# Uc_Ticketing_Slave.net
KiCad netlist of a schematic drawn in Altium Designer
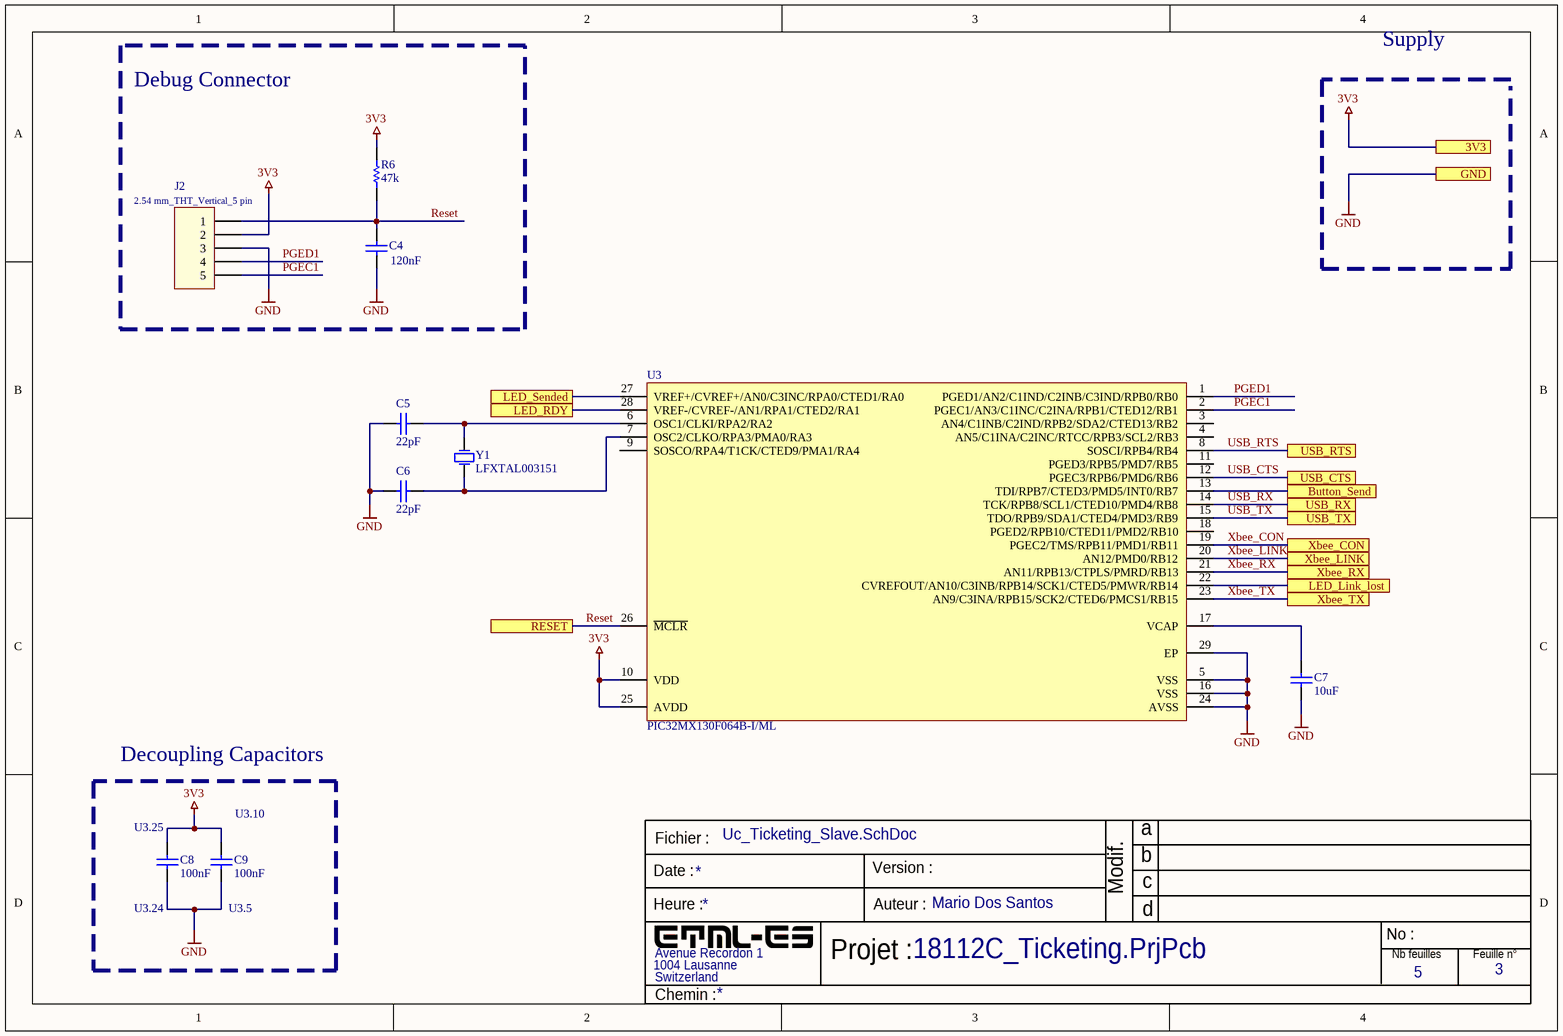
[diagram p0: Uc_Ticketing_Slave.SchDoc]

(export (version "E")
  (design (tool "Eeschema 10.0.6"))
  (components
    (comp (ref "C4")
      (value "120nF")
      (footprint "6-0805_N")
      (description "Capacitor")
      (libsource (lib "Miscellaneous Devices") (part "Cap"))
    )
    (comp (ref "C5")
      (value "22pF")
      (footprint "6-0805_N")
      (description "VJ0805Y104KNAAT")
      (libsource (lib "2126_AffichageMatriciel") (part "CMP-2007-03167-1"))
    )
    (comp (ref "C6")
      (value "22pF")
      (footprint "6-0805_N")
      (description "VJ0805Y104KNAAT")
      (libsource (lib "2126_AffichageMatriciel") (part "CMP-2007-03167-1"))
    )
    (comp (ref "C7")
      (value "10uF")
      (footprint "6-0805_N")
      (description "Capacitor")
      (libsource (lib "Miscellaneous Devices") (part "Cap"))
    )
    (comp (ref "C8")
      (value "100nF")
      (footprint "6-0805_N")
      (description "Capacitor")
      (libsource (lib "Miscellaneous Devices") (part "Cap"))
    )
    (comp (ref "C9")
      (value "100nF")
      (footprint "6-0805_N")
      (description "Capacitor")
      (libsource (lib "Miscellaneous Devices") (part "Cap"))
    )
    (comp (ref "J2")
      (value "2.54 mm_THT_Vertical_5 pin")
      (footprint "61300511121")
      (description "Pin Header WR-PHD, pitch 2.54 mm, THT, Vertical, single row, 5 pin")
      (libsource (lib "ALTIUM-PHD_2_54_THT_PIN_HEADER_6130XX11121-rev18a") (part "61300511121"))
    )
    (comp (ref "R6")
      (value "47k")
      (footprint "RESC0805(2012)_L")
      (description "100K 0.125W 5% 0805 (2012 Metric)  SMD")
      (libsource (lib "Altium Content Vault") (part "CMP-1013-00122-1"))
    )
    (comp (ref "U3")
      (value "PIC32MX130F064B-I/ML")
      (footprint "MCHP-QFN-ML28_L")
      (libsource (lib "PCB_Ticketing_Slave") (part "CMP-0048-00437-1"))
    )
    (comp (ref "Y1")
      (value "LFXTAL003151")
      (footprint "LFXTAL003151REEL")
      (description "Crystal or Oscillator")
      (libsource (lib "2126_AffichageMatriciel") (part "LFXTAL003151REEL"))
    )
  )
  (nets
    (net (code "1") (name "/Button_Send") (class "Default")
      (node (ref "U3") (pin "13") (pinfunction "TDI/RPB7/CTED3/PMD5/INT0/RB7_13") (pintype "passive"))
    )
    (net (code "2") (name "/LED_Link_lost") (class "Default")
      (node (ref "U3") (pin "22") (pinfunction "CVREFOUT/AN10/C3INB/RPB14/SCK1/CTED5/PMWR/RB14_22") (pintype "passive"))
    )
    (net (code "3") (name "/LED_RDY") (class "Default")
      (node (ref "U3") (pin "28") (pinfunction "VREF-/CVREF-/AN1/RPA1/CTED2/RA1_28") (pintype "passive"))
    )
    (net (code "4") (name "/LED_Sended") (class "Default")
      (node (ref "U3") (pin "27") (pinfunction "VREF+/CVREF+/AN0/C3INC/RPA0/CTED1/RA0_27") (pintype "passive"))
    )
    (net (code "5") (name "/PGEC1") (class "Default")
      (node (ref "J2") (pin "5") (pinfunction "5_5") (pintype "passive"))
      (node (ref "U3") (pin "2") (pinfunction "PGEC1/AN3/C1INC/C2INA/RPB1/CTED12/RB1_2") (pintype "passive"))
    )
    (net (code "6") (name "/PGED1") (class "Default")
      (node (ref "J2") (pin "4") (pinfunction "4_4") (pintype "passive"))
      (node (ref "U3") (pin "1") (pinfunction "PGED1/AN2/C1IND/C2INB/C3IND/RPB0/RB0_1") (pintype "passive"))
    )
    (net (code "7") (name "/Reset") (class "Default")
      (node (ref "C4") (pin "2") (pinfunction "2_2") (pintype "passive"))
      (node (ref "J2") (pin "1") (pinfunction "1_1") (pintype "passive"))
      (node (ref "R6") (pin "2") (pinfunction "2_2") (pintype "passive"))
      (node (ref "U3") (pin "26") (pinfunction "~{MCLR}_26") (pintype "passive"))
    )
    (net (code "8") (name "/USB_CTS") (class "Default")
      (node (ref "U3") (pin "12") (pinfunction "PGEC3/RPB6/PMD6/RB6_12") (pintype "passive"))
    )
    (net (code "9") (name "/USB_RTS") (class "Default")
      (node (ref "U3") (pin "8") (pinfunction "SOSCI/RPB4/RB4_8") (pintype "passive"))
    )
    (net (code "10") (name "/USB_RX") (class "Default")
      (node (ref "U3") (pin "14") (pinfunction "TCK/RPB8/SCL1/CTED10/PMD4/RB8_14") (pintype "passive"))
    )
    (net (code "11") (name "/USB_TX") (class "Default")
      (node (ref "U3") (pin "15") (pinfunction "TDO/RPB9/SDA1/CTED4/PMD3/RB9_15") (pintype "passive"))
    )
    (net (code "12") (name "/Xbee_CON") (class "Default")
      (node (ref "U3") (pin "19") (pinfunction "PGEC2/TMS/RPB11/PMD1/RB11_19") (pintype "passive"))
    )
    (net (code "13") (name "/Xbee_LINK") (class "Default")
      (node (ref "U3") (pin "20") (pinfunction "AN12/PMD0/RB12_20") (pintype "passive"))
    )
    (net (code "14") (name "/Xbee_RX") (class "Default")
      (node (ref "U3") (pin "21") (pinfunction "AN11/RPB13/CTPLS/PMRD/RB13_21") (pintype "passive"))
    )
    (net (code "15") (name "/Xbee_TX") (class "Default")
      (node (ref "U3") (pin "23") (pinfunction "AN9/C3INA/RPB15/SCK2/CTED6/PMCS1/RB15_23") (pintype "passive"))
    )
    (net (code "16") (name "3V3") (class "Default")
      (node (ref "C8") (pin "2") (pinfunction "2_2") (pintype "passive"))
      (node (ref "C9") (pin "2") (pinfunction "2_2") (pintype "passive"))
      (node (ref "J2") (pin "2") (pinfunction "2_2") (pintype "passive"))
      (node (ref "R6") (pin "1") (pinfunction "1_1") (pintype "passive"))
      (node (ref "U3") (pin "10") (pinfunction "VDD_10") (pintype "passive"))
      (node (ref "U3") (pin "25") (pinfunction "AVDD_25") (pintype "passive"))
    )
    (net (code "17") (name "GND") (class "Default")
      (node (ref "C4") (pin "1") (pinfunction "1_1") (pintype "passive"))
      (node (ref "C5") (pin "1") (pinfunction "1_1") (pintype "passive"))
      (node (ref "C6") (pin "1") (pinfunction "1_1") (pintype "passive"))
      (node (ref "C7") (pin "1") (pinfunction "1_1") (pintype "passive"))
      (node (ref "C8") (pin "1") (pinfunction "1_1") (pintype "passive"))
      (node (ref "C9") (pin "1") (pinfunction "1_1") (pintype "passive"))
      (node (ref "J2") (pin "3") (pinfunction "3_3") (pintype "passive"))
      (node (ref "U3") (pin "16") (pinfunction "VSS_16") (pintype "passive"))
      (node (ref "U3") (pin "24") (pinfunction "AVSS_24") (pintype "passive"))
      (node (ref "U3") (pin "29") (pinfunction "EP_29") (pintype "passive"))
      (node (ref "U3") (pin "5") (pinfunction "VSS_5") (pintype "passive"))
    )
    (net (code "18") (name "Net-(U3-OSC1{slash}CLKI{slash}RPA2{slash}RA2)") (class "Default")
      (node (ref "C5") (pin "2") (pinfunction "2_2") (pintype "passive"))
      (node (ref "U3") (pin "6") (pinfunction "OSC1/CLKI/RPA2/RA2_6") (pintype "passive"))
      (node (ref "Y1") (pin "1") (pinfunction "1_1") (pintype "passive"))
    )
    (net (code "19") (name "Net-(U3-OSC2{slash}CLKO{slash}RPA3{slash}PMA0{slash}RA3)") (class "Default")
      (node (ref "C6") (pin "2") (pinfunction "2_2") (pintype "passive"))
      (node (ref "U3") (pin "7") (pinfunction "OSC2/CLKO/RPA3/PMA0/RA3_7") (pintype "passive"))
      (node (ref "Y1") (pin "2") (pinfunction "2_2") (pintype "passive"))
    )
    (net (code "20") (name "Net-(U3-VCAP)") (class "Default")
      (node (ref "C7") (pin "2") (pinfunction "2_2") (pintype "passive"))
      (node (ref "U3") (pin "17") (pinfunction "VCAP_17") (pintype "passive"))
    )
    (net (code "21") (name "unconnected-(U3-AN4{slash}C1INB{slash}C2IND{slash}RPB2{slash}SDA2{slash}CTED13{slash}RB2-Pad3)") (class "Default")
      (node (ref "U3") (pin "3") (pinfunction "AN4/C1INB/C2IND/RPB2/SDA2/CTED13/RB2_3") (pintype "passive"))
    )
    (net (code "22") (name "unconnected-(U3-AN5{slash}C1INA{slash}C2INC{slash}RTCC{slash}RPB3{slash}SCL2{slash}RB3-Pad4)") (class "Default")
      (node (ref "U3") (pin "4") (pinfunction "AN5/C1INA/C2INC/RTCC/RPB3/SCL2/RB3_4") (pintype "passive"))
    )
    (net (code "23") (name "unconnected-(U3-PGED2{slash}RPB10{slash}CTED11{slash}PMD2{slash}RB10-Pad18)") (class "Default")
      (node (ref "U3") (pin "18") (pinfunction "PGED2/RPB10/CTED11/PMD2/RB10_18") (pintype "passive"))
    )
    (net (code "24") (name "unconnected-(U3-PGED3{slash}RPB5{slash}PMD7{slash}RB5-Pad11)") (class "Default")
      (node (ref "U3") (pin "11") (pinfunction "PGED3/RPB5/PMD7/RB5_11") (pintype "passive"))
    )
    (net (code "25") (name "unconnected-(U3-SOSCO{slash}RPA4{slash}T1CK{slash}CTED9{slash}PMA1{slash}RA4-Pad9)") (class "Default")
      (node (ref "U3") (pin "9") (pinfunction "SOSCO/RPA4/T1CK/CTED9/PMA1/RA4_9") (pintype "passive"))
    )
  )
)
